# Homefi_10.net
KiCad netlist of a schematic drawn in EAGLE
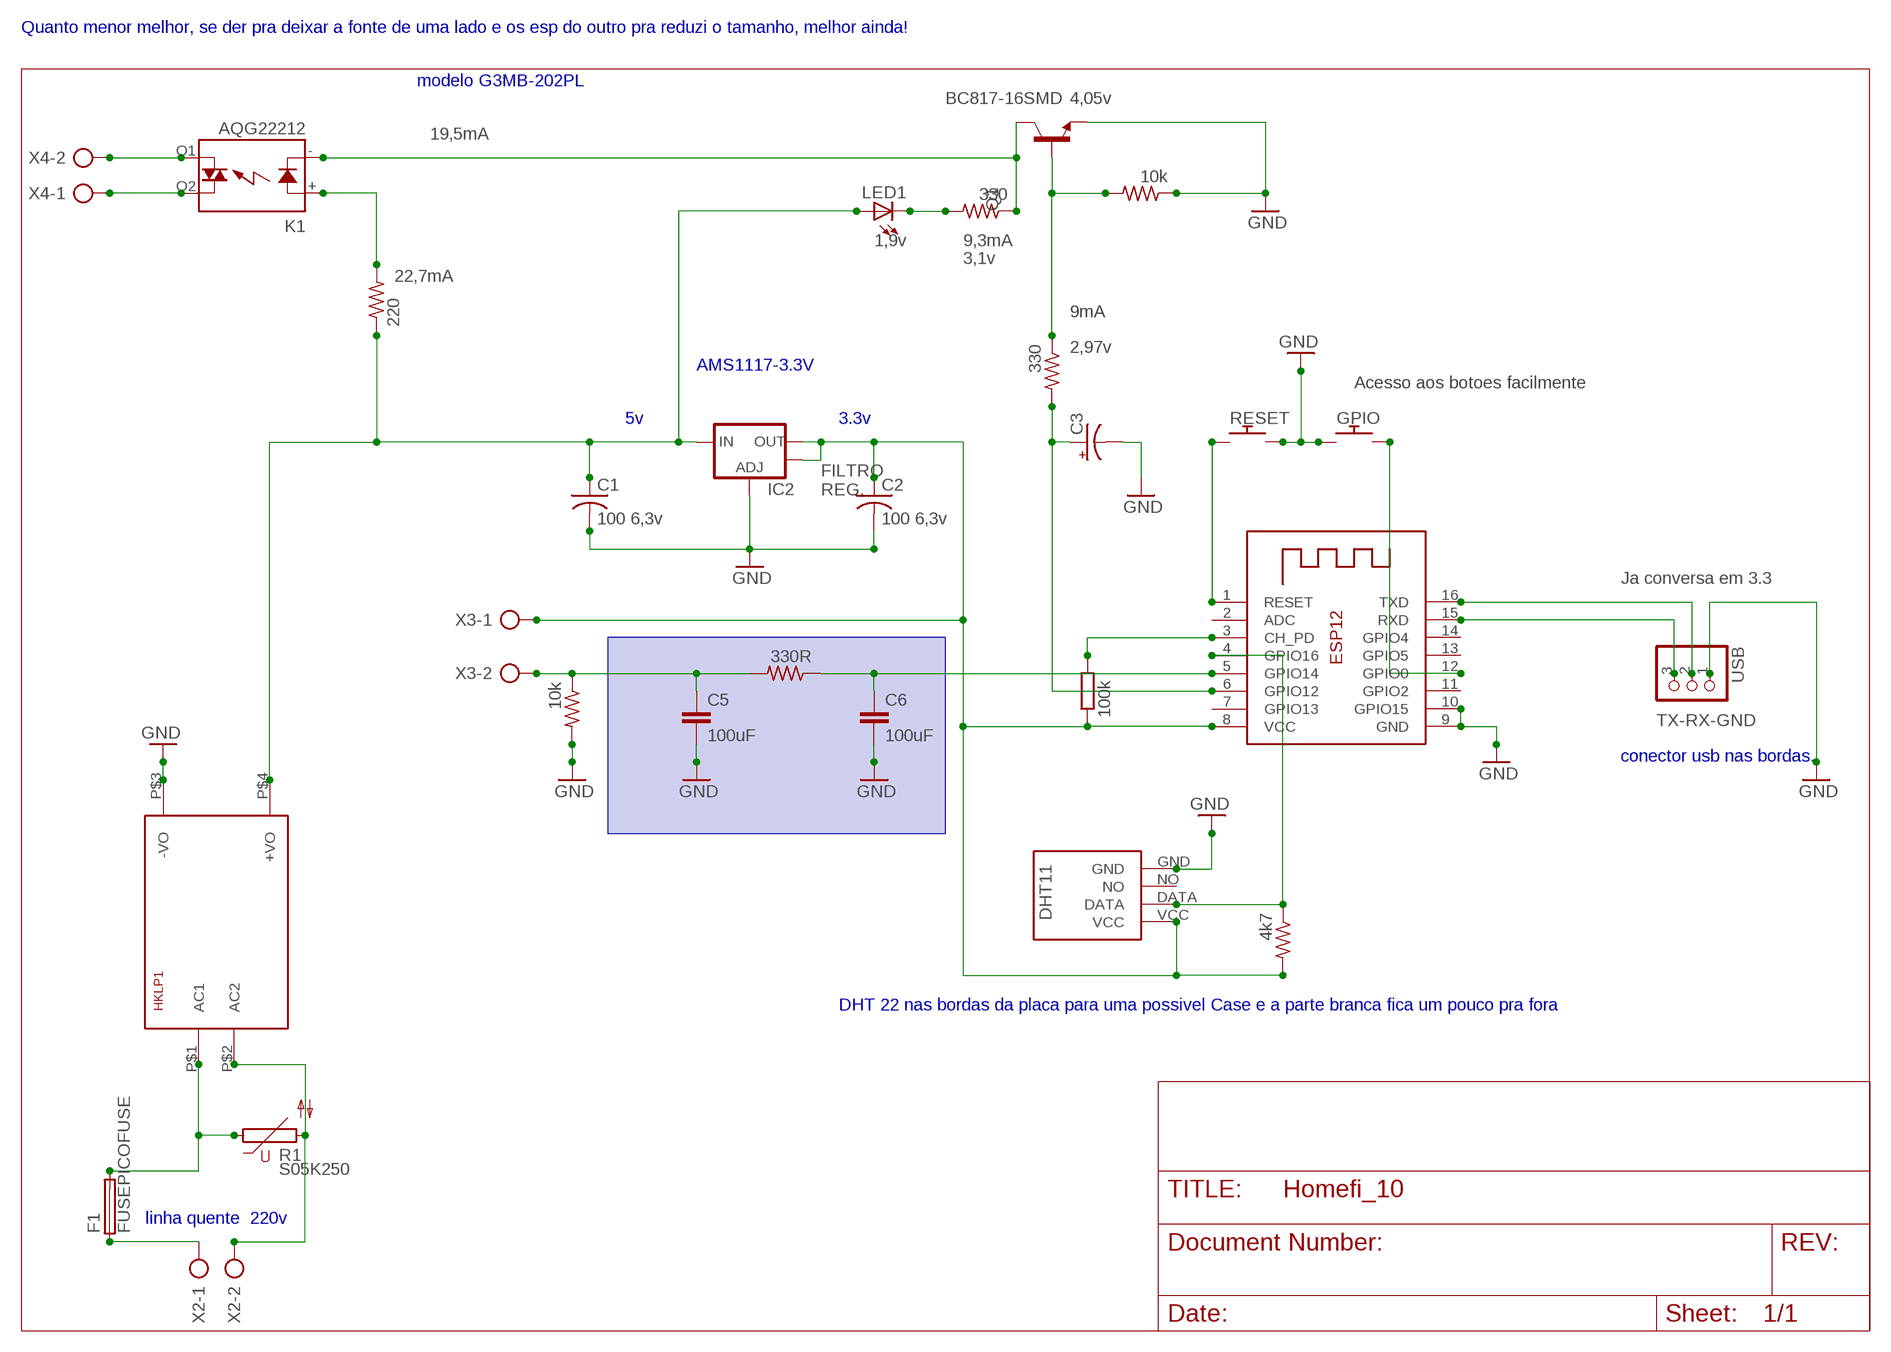
[diagram p0: schematic, sheet 1]

(export (version "E")
  (design (tool "Eeschema 10.0.6"))
  (components
    (comp (ref "1")
      (value "10k")
      (footprint "eagle-import:M0805")
      (libsource (lib "eagle-import") (part "R-US_M0805"))
    )
    (comp (ref "2")
      (value "10k")
      (footprint "eagle-import:M0805")
      (libsource (lib "eagle-import") (part "R-US_M0805"))
    )
    (comp (ref "3")
      (value "100k")
      (footprint "eagle-import:M0805")
      (libsource (lib "eagle-import") (part "R-EU_M0805"))
    )
    (comp (ref "4")
      (value "330R")
      (footprint "eagle-import:M0805")
      (libsource (lib "eagle-import") (part "R-US_M0805"))
    )
    (comp (ref "5")
      (value "330")
      (footprint "eagle-import:M0805")
      (libsource (lib "eagle-import") (part "R-US_M0805"))
    )
    (comp (ref "6")
      (value "220")
      (footprint "eagle-import:M0805")
      (libsource (lib "eagle-import") (part "R-US_M0805"))
    )
    (comp (ref "7")
      (value "330")
      (footprint "eagle-import:M0805")
      (libsource (lib "eagle-import") (part "R-US_M0805"))
    )
    (comp (ref "8")
      (value "4k7")
      (footprint "eagle-import:M0805")
      (libsource (lib "eagle-import") (part "R-US_M0805"))
    )
    (comp (ref "C1")
      (value "100 6,3v")
      (footprint "eagle-import:C0805")
      (libsource (lib "eagle-import") (part "C-USC0805"))
    )
    (comp (ref "C2")
      (value "100 6,3v")
      (footprint "eagle-import:C0805")
      (libsource (lib "eagle-import") (part "C-USC0805"))
    )
    (comp (ref "C3")
      (value "CPOL-US153CLV-0605")
      (footprint "eagle-import:153CLV-0605")
      (libsource (lib "eagle-import") (part "CPOL-US153CLV-0605"))
    )
    (comp (ref "C5")
      (value "100uF")
      (footprint "eagle-import:C0805")
      (libsource (lib "eagle-import") (part "C-EUC0805"))
    )
    (comp (ref "C6")
      (value "100uF")
      (footprint "eagle-import:C0805")
      (libsource (lib "eagle-import") (part "C-EUC0805"))
    )
    (comp (ref "F1")
      (value "FUSEPICOFUSE")
      (footprint "eagle-import:PICOFUSE")
      (libsource (lib "eagle-import") (part "FUSEPICOFUSE"))
    )
    (comp (ref "GPIO")
      (value "GPIO")
      (footprint "eagle-import:TACT_PANA-EVQ")
      (libsource (lib "eagle-import") (part "SWITCH_PUSHBUTTONEVQ-PE"))
    )
    (comp (ref "HKLP1")
      (value "HKLPM01")
      (footprint "eagle-import:HKLPM01")
      (libsource (lib "eagle-import") (part "HKLPM01"))
    )
    (comp (ref "IC2")
      (value "V_REG_LM1117SOT223")
      (footprint "eagle-import:SOT223")
      (libsource (lib "eagle-import") (part "V_REG_LM1117SOT223"))
    )
    (comp (ref "K1")
      (value "AQG22212")
      (footprint "eagle-import:AQG")
      (libsource (lib "eagle-import") (part "AQG22212"))
    )
    (comp (ref "LED1")
      (value "LEDCHIPLED_0805")
      (footprint "eagle-import:CHIPLED_0805")
      (libsource (lib "eagle-import") (part "LEDCHIPLED_0805"))
    )
    (comp (ref "Q1")
      (value "BC817-16SMD")
      (footprint "eagle-import:SOT23-BEC")
      (libsource (lib "eagle-import") (part "BC817SMD-16"))
    )
    (comp (ref "R1")
      (value "S05K250")
      (footprint "eagle-import:S05K250")
      (libsource (lib "eagle-import") (part "S05K250"))
    )
    (comp (ref "RESET")
      (value "RESET")
      (footprint "eagle-import:TACT_PANA-EVQ")
      (libsource (lib "eagle-import") (part "SWITCH_PUSHBUTTONEVQ-PE"))
    )
    (comp (ref "U$1")
      (value "DHT11-PION.")
      (footprint "eagle-import:DHT11-PION.")
      (libsource (lib "eagle-import") (part "DHT11-PION."))
    )
    (comp (ref "USB")
      (value "PINHD-1X3")
      (footprint "eagle-import:1X03")
      (libsource (lib "eagle-import") (part "PINHD-1X3"))
    )
    (comp (ref "X2")
      (value "AK500/2")
      (footprint "eagle-import:AK500_2")
      (libsource (lib "eagle-import") (part "AK500/2"))
    )
    (comp (ref "X3")
      (value "AK500/2")
      (footprint "eagle-import:AK500_2")
      (libsource (lib "eagle-import") (part "AK500/2"))
    )
    (comp (ref "X4")
      (value "AK500/2")
      (footprint "eagle-import:AK500_2")
      (libsource (lib "eagle-import") (part "AK500/2"))
    )
    (comp (ref "X5")
      (value "ESP-12")
      (footprint "eagle-import:ESP-12")
      (libsource (lib "eagle-import") (part "ESP-12"))
    )
  )
  (nets
    (net (code "1") (name "GND") (class "Default")
      (node (ref "1") (pin "1") (pinfunction "1_1") (pintype "passive"))
      (node (ref "2") (pin "2") (pinfunction "2_2") (pintype "passive"))
      (node (ref "C1") (pin "2") (pinfunction "2_2") (pintype "passive"))
      (node (ref "C2") (pin "2") (pinfunction "2_2") (pintype "passive"))
      (node (ref "C3") (pin "-") (pinfunction "-_-") (pintype "passive"))
      (node (ref "C5") (pin "2") (pinfunction "2_2") (pintype "passive"))
      (node (ref "C6") (pin "2") (pinfunction "2_2") (pintype "passive"))
      (node (ref "GPIO") (pin "P$1") (pinfunction "P$1_P$1") (pintype "passive"))
      (node (ref "HKLP1") (pin "P$3") (pinfunction "-VO_P$3") (pintype "bidirectional"))
      (node (ref "IC2") (pin "1") (pinfunction "ADJ_1") (pintype "input"))
      (node (ref "Q1") (pin "E") (pinfunction "E_E") (pintype "passive"))
      (node (ref "RESET") (pin "P$2") (pinfunction "P$2_P$2") (pintype "passive"))
      (node (ref "U$1") (pin "GND") (pinfunction "GND_GND") (pintype "bidirectional"))
      (node (ref "USB") (pin "1") (pinfunction "1_1") (pintype "passive"))
      (node (ref "X5") (pin "10") (pinfunction "GPIO15_10") (pintype "bidirectional"))
      (node (ref "X5") (pin "9") (pinfunction "GND_9") (pintype "power_in"))
    )
    (net (code "2") (name "Net-(1-Pad2)") (class "Default")
      (node (ref "1") (pin "2") (pinfunction "2_2") (pintype "passive"))
      (node (ref "7") (pin "1") (pinfunction "1_1") (pintype "passive"))
      (node (ref "Q1") (pin "B") (pinfunction "B_B") (pintype "passive"))
    )
    (net (code "3") (name "Net-(5-Pad2)") (class "Default")
      (node (ref "5") (pin "2") (pinfunction "2_2") (pintype "passive"))
      (node (ref "LED1") (pin "C") (pinfunction "C_C") (pintype "passive"))
    )
    (net (code "4") (name "Net-(HKLP1-+VO)") (class "Default")
      (node (ref "6") (pin "1") (pinfunction "1_1") (pintype "passive"))
      (node (ref "C1") (pin "1") (pinfunction "1_1") (pintype "passive"))
      (node (ref "HKLP1") (pin "P$4") (pinfunction "+VO_P$4") (pintype "bidirectional"))
      (node (ref "IC2") (pin "3") (pinfunction "IN_3") (pintype "input"))
      (node (ref "LED1") (pin "A") (pinfunction "A_A") (pintype "passive"))
    )
    (net (code "5") (name "Net-(HKLP1-AC1)") (class "Default")
      (node (ref "F1") (pin "2") (pinfunction "2_2") (pintype "passive"))
      (node (ref "HKLP1") (pin "P$1") (pinfunction "AC1_P$1") (pintype "bidirectional"))
      (node (ref "R1") (pin "1") (pinfunction "1_1") (pintype "passive"))
    )
    (net (code "6") (name "Net-(HKLP1-AC2)") (class "Default")
      (node (ref "HKLP1") (pin "P$2") (pinfunction "AC2_P$2") (pintype "bidirectional"))
      (node (ref "R1") (pin "2") (pinfunction "2_2") (pintype "passive"))
      (node (ref "X2") (pin "2") (pinfunction "KL_2") (pintype "passive"))
    )
    (net (code "7") (name "Net-(K1-A)") (class "Default")
      (node (ref "6") (pin "2") (pinfunction "2_2") (pintype "passive"))
      (node (ref "K1") (pin "+") (pinfunction "A_+") (pintype "passive"))
    )
    (net (code "8") (name "Net-(K1-DS1)") (class "Default")
      (node (ref "K1") (pin "O2") (pinfunction "DS1_O2") (pintype "passive"))
      (node (ref "X4") (pin "1") (pinfunction "KL_1") (pintype "passive"))
    )
    (net (code "9") (name "Net-(K1-DS2)") (class "Default")
      (node (ref "K1") (pin "O1") (pinfunction "DS2_O1") (pintype "passive"))
      (node (ref "X4") (pin "2") (pinfunction "KL_2") (pintype "passive"))
    )
    (net (code "10") (name "Net-(K1-K)") (class "Default")
      (node (ref "5") (pin "1") (pinfunction "1_1") (pintype "passive"))
      (node (ref "K1") (pin "-") (pinfunction "K_-") (pintype "passive"))
      (node (ref "Q1") (pin "C") (pinfunction "C_C") (pintype "passive"))
    )
    (net (code "11") (name "Net-(X2A-KL)") (class "Default")
      (node (ref "F1") (pin "1") (pinfunction "1_1") (pintype "passive"))
      (node (ref "X2") (pin "1") (pinfunction "KL_1") (pintype "passive"))
    )
    (net (code "12") (name "Net-(X3A-KL)") (class "Default")
      (node (ref "3") (pin "1") (pinfunction "1_1") (pintype "passive"))
      (node (ref "8") (pin "2") (pinfunction "2_2") (pintype "passive"))
      (node (ref "C2") (pin "1") (pinfunction "1_1") (pintype "passive"))
      (node (ref "IC2") (pin "2") (pinfunction "OUT_2") (pintype "output"))
      (node (ref "IC2") (pin "4") (pinfunction "OUT_4") (pintype "output"))
      (node (ref "U$1") (pin "VCC") (pinfunction "VCC_VCC") (pintype "bidirectional"))
      (node (ref "X3") (pin "1") (pinfunction "KL_1") (pintype "passive"))
      (node (ref "X5") (pin "8") (pinfunction "VCC_8") (pintype "power_in"))
    )
    (net (code "13") (name "Net-(X3B-KL)") (class "Default")
      (node (ref "2") (pin "1") (pinfunction "1_1") (pintype "passive"))
      (node (ref "4") (pin "2") (pinfunction "2_2") (pintype "passive"))
      (node (ref "C5") (pin "1") (pinfunction "1_1") (pintype "passive"))
      (node (ref "X3") (pin "2") (pinfunction "KL_2") (pintype "passive"))
    )
    (net (code "14") (name "Net-(X5-CH_PD)") (class "Default")
      (node (ref "3") (pin "2") (pinfunction "2_2") (pintype "passive"))
      (node (ref "X5") (pin "3") (pinfunction "CH_PD_3") (pintype "input"))
    )
    (net (code "15") (name "Net-(X5-GPIO0)") (class "Default")
      (node (ref "GPIO") (pin "P$2") (pinfunction "P$2_P$2") (pintype "passive"))
      (node (ref "X5") (pin "12") (pinfunction "GPIO0_12") (pintype "bidirectional"))
    )
    (net (code "16") (name "Net-(X5-GPIO12)") (class "Default")
      (node (ref "7") (pin "2") (pinfunction "2_2") (pintype "passive"))
      (node (ref "C3") (pin "+") (pinfunction "+_+") (pintype "passive"))
      (node (ref "X5") (pin "6") (pinfunction "GPIO12_6") (pintype "bidirectional"))
    )
    (net (code "17") (name "Net-(X5-GPIO14)") (class "Default")
      (node (ref "4") (pin "1") (pinfunction "1_1") (pintype "passive"))
      (node (ref "C6") (pin "1") (pinfunction "1_1") (pintype "passive"))
      (node (ref "X5") (pin "5") (pinfunction "GPIO14_5") (pintype "bidirectional"))
    )
    (net (code "18") (name "Net-(X5-GPIO16)") (class "Default")
      (node (ref "8") (pin "1") (pinfunction "1_1") (pintype "passive"))
      (node (ref "U$1") (pin "DATA") (pinfunction "DATA_DATA") (pintype "bidirectional"))
      (node (ref "X5") (pin "4") (pinfunction "GPIO16_4") (pintype "bidirectional"))
    )
    (net (code "19") (name "Net-(X5-RESET)") (class "Default")
      (node (ref "RESET") (pin "P$1") (pinfunction "P$1_P$1") (pintype "passive"))
      (node (ref "X5") (pin "1") (pinfunction "RESET_1") (pintype "input"))
    )
    (net (code "20") (name "Net-(X5-RXD)") (class "Default")
      (node (ref "USB") (pin "3") (pinfunction "3_3") (pintype "passive"))
      (node (ref "X5") (pin "15") (pinfunction "RXD_15") (pintype "input"))
    )
    (net (code "21") (name "Net-(X5-TXD)") (class "Default")
      (node (ref "USB") (pin "2") (pinfunction "2_2") (pintype "passive"))
      (node (ref "X5") (pin "16") (pinfunction "TXD_16") (pintype "output"))
    )
    (net (code "22") (name "unconnected-(U$1-PadNO)") (class "Default")
      (node (ref "U$1") (pin "NO") (pinfunction "NO_NO") (pintype "bidirectional"))
    )
    (net (code "23") (name "unconnected-(X5-ADC-Pad2)") (class "Default")
      (node (ref "X5") (pin "2") (pinfunction "ADC_2") (pintype "passive"))
    )
    (net (code "24") (name "unconnected-(X5-GPIO2-Pad11)") (class "Default")
      (node (ref "X5") (pin "11") (pinfunction "GPIO2_11") (pintype "bidirectional"))
    )
    (net (code "25") (name "unconnected-(X5-GPIO4-Pad14)") (class "Default")
      (node (ref "X5") (pin "14") (pinfunction "GPIO4_14") (pintype "bidirectional"))
    )
    (net (code "26") (name "unconnected-(X5-GPIO5-Pad13)") (class "Default")
      (node (ref "X5") (pin "13") (pinfunction "GPIO5_13") (pintype "bidirectional"))
    )
    (net (code "27") (name "unconnected-(X5-GPIO13-Pad7)") (class "Default")
      (node (ref "X5") (pin "7") (pinfunction "GPIO13_7") (pintype "bidirectional"))
    )
  )
)
